# ProPrj_usb__2025-12-09-23-03-54.net
KiCad netlist of a schematic drawn in EasyEDA Pro
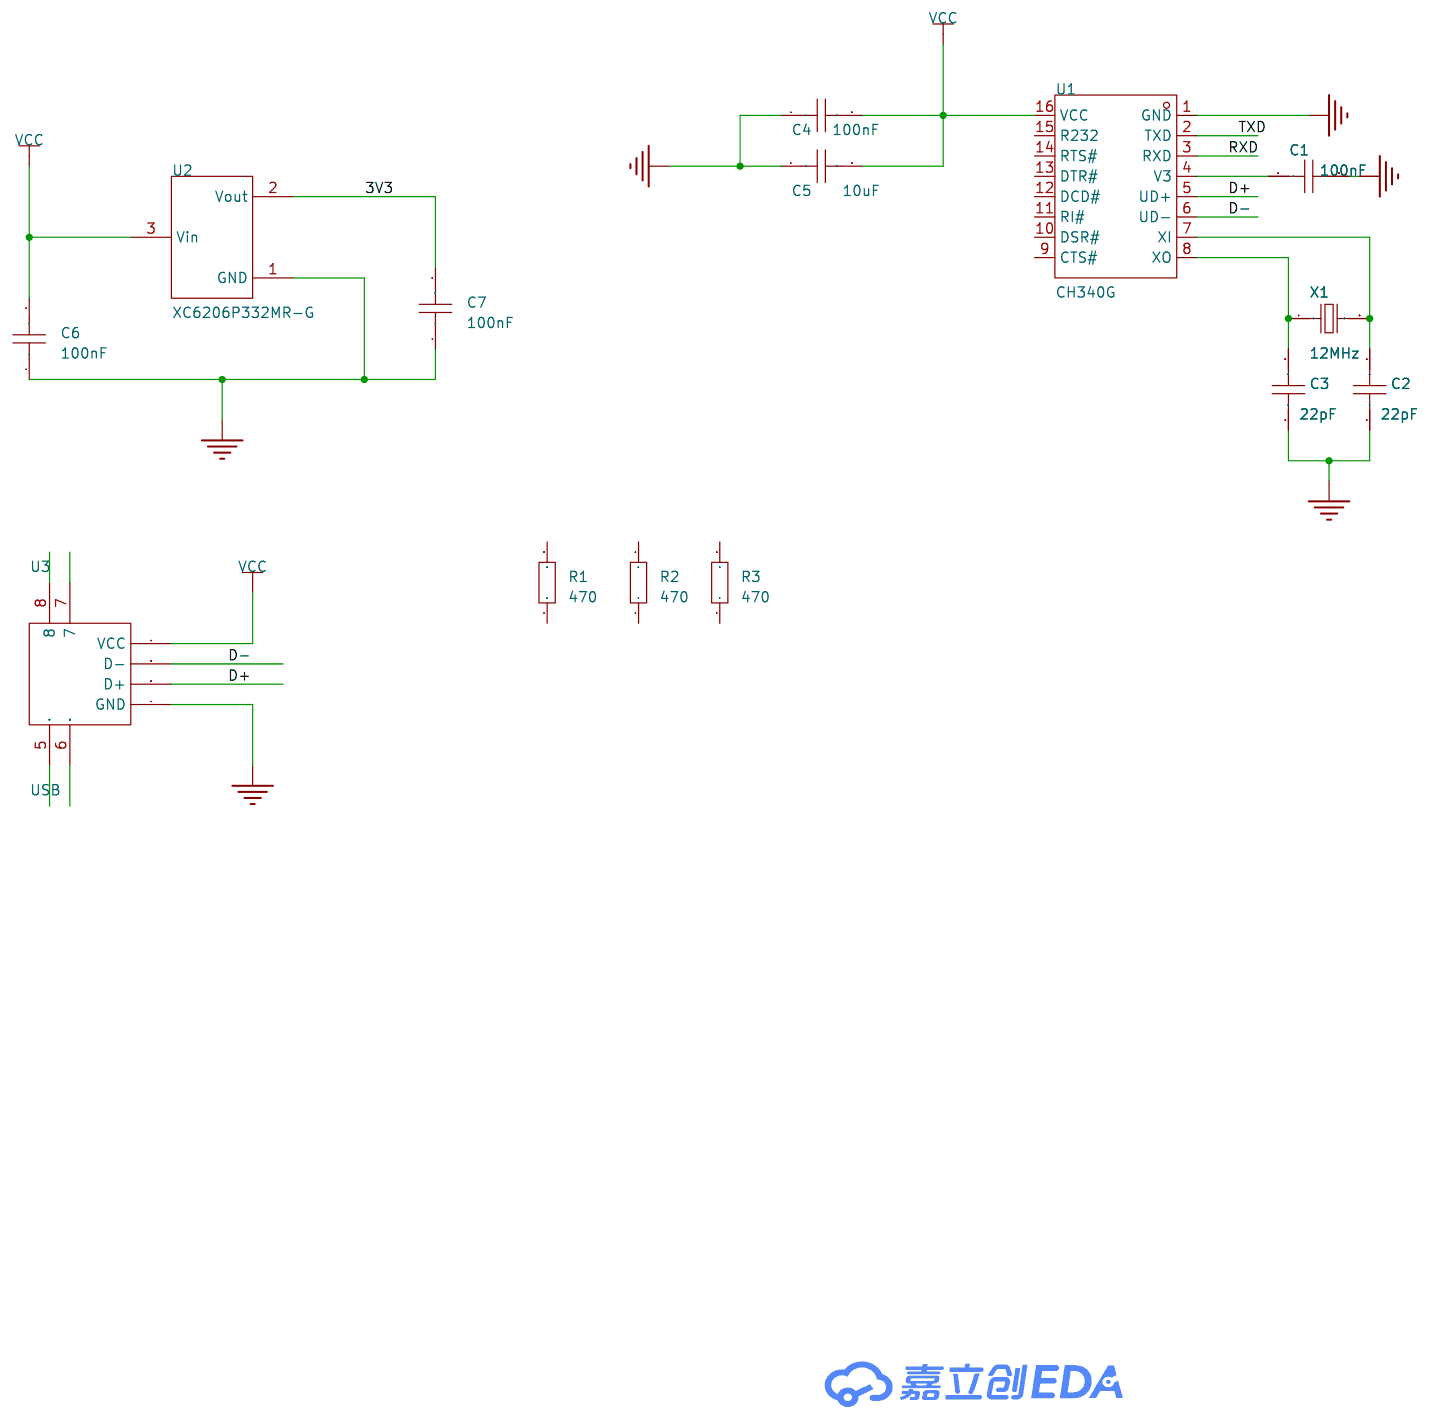
[diagram p0: schematic sheet]

(export (version "E")
  (design (tool "Eeschema 10.0.6"))
  (components
    (comp (ref "C1")
      (value "100nF")
      (footprint "easyedapro:C0603")
      (libsource (lib "easyedapro") (part "Capacitance"))
    )
    (comp (ref "C2")
      (value "22pF")
      (footprint "easyedapro:C0603")
      (libsource (lib "easyedapro") (part "Capacitance"))
    )
    (comp (ref "C3")
      (value "22pF")
      (footprint "easyedapro:C0603")
      (libsource (lib "easyedapro") (part "Capacitance"))
    )
    (comp (ref "C4")
      (value "100nF")
      (footprint "easyedapro:C0603")
      (libsource (lib "easyedapro") (part "Capacitance"))
    )
    (comp (ref "C5")
      (value "10uF")
      (footprint "easyedapro:C0603")
      (libsource (lib "easyedapro") (part "Capacitance"))
    )
    (comp (ref "C6")
      (value "100nF")
      (footprint "easyedapro:C0603")
      (libsource (lib "easyedapro") (part "Capacitance"))
    )
    (comp (ref "C7")
      (value "100nF")
      (footprint "easyedapro:C0603")
      (libsource (lib "easyedapro") (part "Capacitance"))
    )
    (comp (ref "R1") (value "470") (footprint "easyedapro:R0603") (libsource (lib "easyedapro") (part "电阻")))
    (comp (ref "R2") (value "470") (footprint "easyedapro:R0603") (libsource (lib "easyedapro") (part "电阻")))
    (comp (ref "R3") (value "470") (footprint "easyedapro:R0603") (libsource (lib "easyedapro") (part "电阻")))
    (comp (ref "U1")
      (value "CH340G")
      (footprint "easyedapro:SOIC-16_L9.9-W3.9-P1.27-LS6.0-BL")
      (description "应用功能:USB转UART;接口协议:USB 2.0;数据速率:2Mbps;")
      (fields (field (name "Manufacturer") "WCH(南京沁恒)"))
      (libsource (lib "easyedapro") (part "CH340G"))
    )
    (comp (ref "U2")
      (value "XC6206P332MR-G")
      (footprint "easyedapro:SOT-23-3_L2.9-W1.6-P1.90-LS2.8-BR")
      (description "输出类型:固定;工作电压:6V;输出电压:3.3V;输出电流:200mA;电源纹波抑制比(PSRR):-;输出极性:正极;")
      (fields (field (name "Manufacturer") "TOREX(特瑞仕)"))
      (libsource (lib "easyedapro") (part "XC6206P332MR"))
    )
    (comp (ref "U3")
      (value "USB")
      (footprint "easyedapro:USB-SMD_USB_1")
      (libsource (lib "easyedapro") (part "USB"))
    )
    (comp (ref "X1")
      (value "12MHz")
      (footprint "easyedapro:CRYSTAL-SMD_L5.0-W3.2")
      (description "晶振类型:贴片晶振;频率:12MHz;常温频差:±20ppm;负载电容:20pF;频率稳定度:±30ppm;")
      (fields
        (field (name "Manufacturer Part") "XC53G2-12.000-F20LJDT")
        (field (name "Manufacturer") "HCI(杭晶)")
      )
      (libsource (lib "easyedapro") (part "XC53G2-12.000-F20LJDT"))
    )
  )
  (nets
    (net (code "1") (name "/3V3") (class "Default")
      (node (ref "C7") (pin "2") (pinfunction "2_2") (pintype "input"))
      (node (ref "U2") (pin "2") (pinfunction "Vout_2") (pintype "unspecified"))
    )
    (net (code "2") (name "/D+") (class "Default")
      (node (ref "U1") (pin "5") (pinfunction "UD+_5") (pintype "unspecified"))
      (node (ref "U3") (pin "3") (pinfunction "D+_3") (pintype "input"))
    )
    (net (code "3") (name "/D-") (class "Default")
      (node (ref "U1") (pin "6") (pinfunction "UD-_6") (pintype "unspecified"))
      (node (ref "U3") (pin "2") (pinfunction "D-_2") (pintype "input"))
    )
    (net (code "4") (name "/RXD") (class "Default")
      (node (ref "U1") (pin "3") (pinfunction "RXD_3") (pintype "unspecified"))
    )
    (net (code "5") (name "/TXD") (class "Default")
      (node (ref "U1") (pin "2") (pinfunction "TXD_2") (pintype "unspecified"))
    )
    (net (code "6") (name "GND") (class "Default")
      (node (ref "C1") (pin "2") (pinfunction "2_2") (pintype "input"))
      (node (ref "C2") (pin "1") (pinfunction "1_1") (pintype "input"))
      (node (ref "C3") (pin "1") (pinfunction "1_1") (pintype "input"))
      (node (ref "C4") (pin "1") (pinfunction "1_1") (pintype "input"))
      (node (ref "C5") (pin "1") (pinfunction "1_1") (pintype "input"))
      (node (ref "C6") (pin "1") (pinfunction "1_1") (pintype "input"))
      (node (ref "C7") (pin "1") (pinfunction "1_1") (pintype "input"))
      (node (ref "U1") (pin "1") (pinfunction "GND_1") (pintype "unspecified"))
      (node (ref "U2") (pin "1") (pinfunction "GND_1") (pintype "unspecified"))
      (node (ref "U3") (pin "4") (pinfunction "GND_4") (pintype "input"))
    )
    (net (code "7") (name "Net-(U1-V3)") (class "Default")
      (node (ref "C1") (pin "1") (pinfunction "1_1") (pintype "input"))
      (node (ref "U1") (pin "4") (pinfunction "V3_4") (pintype "unspecified"))
    )
    (net (code "8") (name "Net-(U1-XI)") (class "Default")
      (node (ref "C2") (pin "2") (pinfunction "2_2") (pintype "input"))
      (node (ref "U1") (pin "7") (pinfunction "XI_7") (pintype "unspecified"))
      (node (ref "X1") (pin "2") (pinfunction "2_2") (pintype "unspecified"))
    )
    (net (code "9") (name "Net-(U1-XO)") (class "Default")
      (node (ref "C3") (pin "2") (pinfunction "2_2") (pintype "input"))
      (node (ref "U1") (pin "8") (pinfunction "XO_8") (pintype "unspecified"))
      (node (ref "X1") (pin "1") (pinfunction "1_1") (pintype "unspecified"))
    )
    (net (code "10") (name "VCC") (class "Default")
      (node (ref "C4") (pin "2") (pinfunction "2_2") (pintype "input"))
      (node (ref "C5") (pin "2") (pinfunction "2_2") (pintype "input"))
      (node (ref "C6") (pin "2") (pinfunction "2_2") (pintype "input"))
      (node (ref "U1") (pin "16") (pinfunction "VCC_16") (pintype "unspecified"))
      (node (ref "U2") (pin "3") (pinfunction "Vin_3") (pintype "unspecified"))
      (node (ref "U3") (pin "1") (pinfunction "VCC_1") (pintype "input"))
    )
    (net (code "11") (name "unconnected-(R1-Pad1)") (class "Default")
      (node (ref "R1") (pin "1") (pinfunction "1_1") (pintype "input"))
    )
    (net (code "12") (name "unconnected-(R1-Pad2)") (class "Default")
      (node (ref "R1") (pin "2") (pinfunction "2_2") (pintype "input"))
    )
    (net (code "13") (name "unconnected-(R2-Pad1)") (class "Default")
      (node (ref "R2") (pin "1") (pinfunction "1_1") (pintype "input"))
    )
    (net (code "14") (name "unconnected-(R2-Pad2)") (class "Default")
      (node (ref "R2") (pin "2") (pinfunction "2_2") (pintype "input"))
    )
    (net (code "15") (name "unconnected-(R3-Pad1)") (class "Default")
      (node (ref "R3") (pin "1") (pinfunction "1_1") (pintype "input"))
    )
    (net (code "16") (name "unconnected-(R3-Pad2)") (class "Default")
      (node (ref "R3") (pin "2") (pinfunction "2_2") (pintype "input"))
    )
    (net (code "17") (name "unconnected-(U1-CTS#-Pad9)") (class "Default")
      (node (ref "U1") (pin "9") (pinfunction "CTS#_9") (pintype "unspecified"))
    )
    (net (code "18") (name "unconnected-(U1-DCD#-Pad12)") (class "Default")
      (node (ref "U1") (pin "12") (pinfunction "DCD#_12") (pintype "unspecified"))
    )
    (net (code "19") (name "unconnected-(U1-DSR#-Pad10)") (class "Default")
      (node (ref "U1") (pin "10") (pinfunction "DSR#_10") (pintype "unspecified"))
    )
    (net (code "20") (name "unconnected-(U1-DTR#-Pad13)") (class "Default")
      (node (ref "U1") (pin "13") (pinfunction "DTR#_13") (pintype "unspecified"))
    )
    (net (code "21") (name "unconnected-(U1-R232-Pad15)") (class "Default")
      (node (ref "U1") (pin "15") (pinfunction "R232_15") (pintype "unspecified"))
    )
    (net (code "22") (name "unconnected-(U1-RI#-Pad11)") (class "Default")
      (node (ref "U1") (pin "11") (pinfunction "RI#_11") (pintype "unspecified"))
    )
    (net (code "23") (name "unconnected-(U1-RTS#-Pad14)") (class "Default")
      (node (ref "U1") (pin "14") (pinfunction "RTS#_14") (pintype "unspecified"))
    )
    (net (code "24") (name "unconnected-(U3-Pad7)") (class "Default")
      (node (ref "U3") (pin "7") (pinfunction "7_7") (pintype "unspecified"))
    )
    (net (code "25") (name "unconnected-(U3-Pad8)") (class "Default")
      (node (ref "U3") (pin "8") (pinfunction "8_8") (pintype "unspecified"))
    )
    (net (code "26") (name "unconnected-(U3-SH1-Pad5)") (class "Default")
      (node (ref "U3") (pin "5") (pinfunction "SH1_5") (pintype "unspecified"))
    )
    (net (code "27") (name "unconnected-(U3-SH2-Pad6)") (class "Default")
      (node (ref "U3") (pin "6") (pinfunction "SH2_6") (pintype "unspecified"))
    )
  )
)
